# GniMp3.net
KiCad netlist of a schematic drawn in Altium Designer
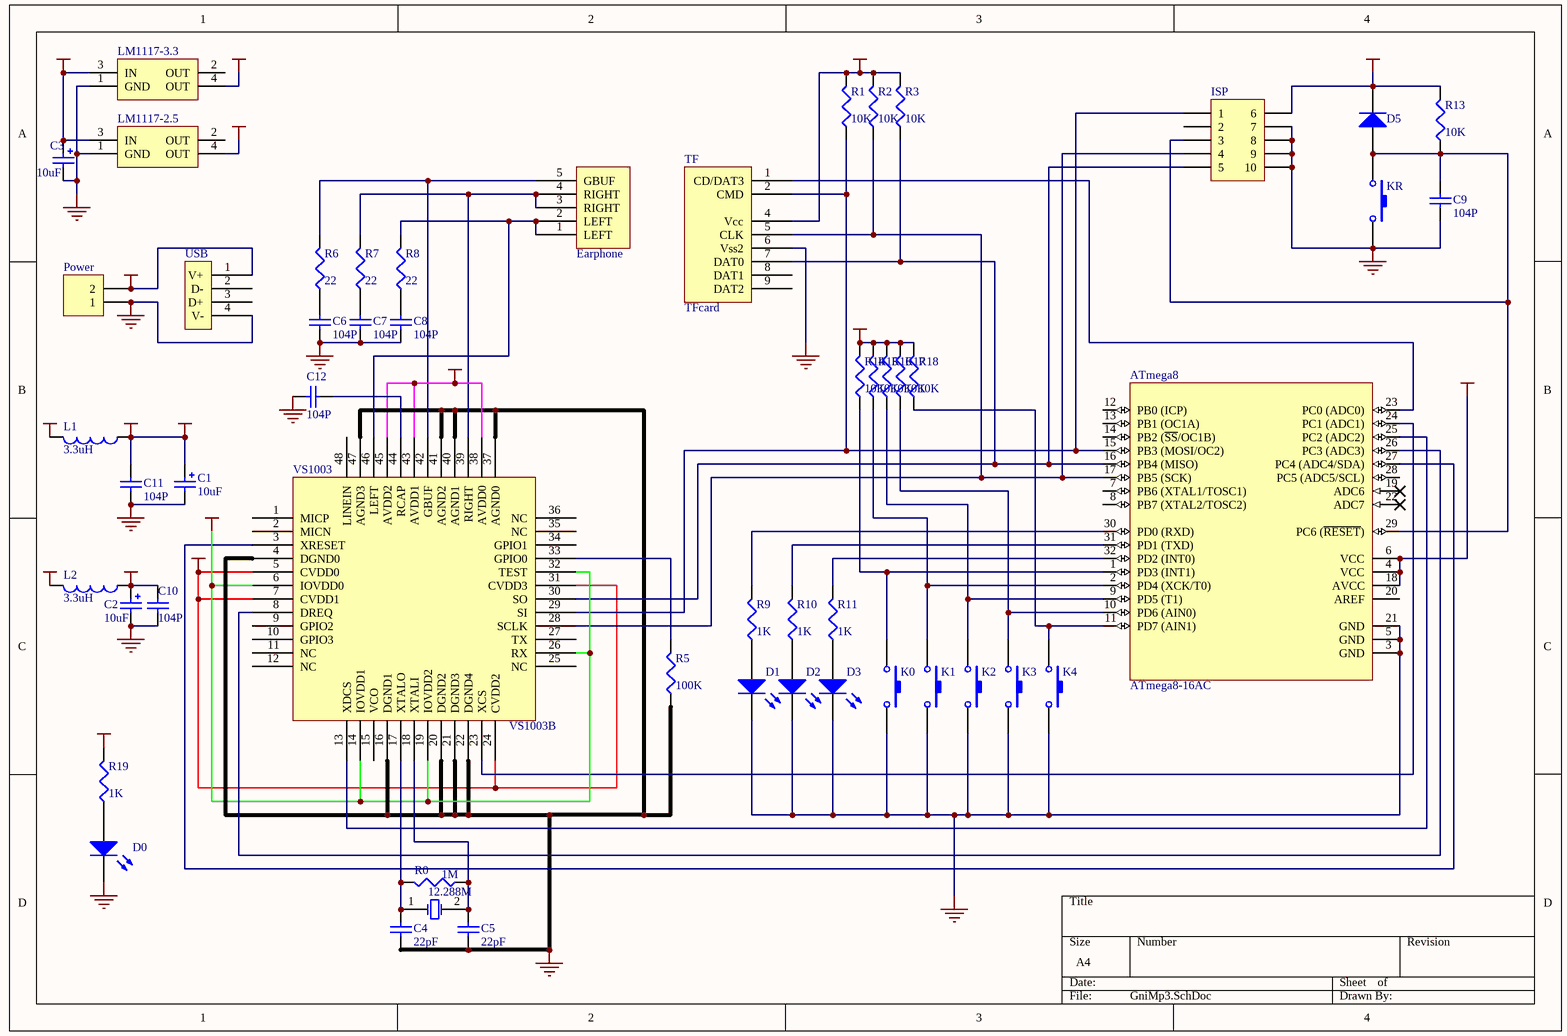
[diagram p0: GniMp3.SchDoc]

(export (version "E")
  (design (tool "Eeschema 10.0.6"))
  (components
    (comp (ref "12.288M")
      (value "XTAL")
      (footprint "RAD-0.2")
      (description "Crystal Oscillator")
      (fields (field (name "PUBLISHER") "Altium Limited"))
      (libsource (lib "Miscellaneous Devices") (part "XTAL"))
    )
    (comp (ref "ATmega8")
      (value "ATmega8-16AC")
      (footprint "32A")
      (description "8-Bit AVR Microcontroller with 8K Bytes of In-System Programmable Flash Memory")
      (fields (field (name "PUBLISHER") "Altium Limited"))
      (libsource (lib "Atmel Microcontroller 8-Bit AVR") (part "ATmega8-16AC"))
    )
    (comp (ref "C1")
      (value "10uF")
      (footprint "CC3225-1210")
      (description "Polarized Capacitor (Surface Mount)")
      (fields (field (name "Comment") "Cap Pol3") (field (name "PUBLISHER") "Altium Limited"))
      (libsource (lib "Miscellaneous Devices") (part "Cap Pol3"))
    )
    (comp (ref "C2")
      (value "10uF")
      (footprint "CR3225-1210")
      (description "Polarized Capacitor (Surface Mount)")
      (fields (field (name "Comment") "Cap Pol3") (field (name "PUBLISHER") "Altium Limited"))
      (libsource (lib "Miscellaneous Devices") (part "Cap Pol3"))
    )
    (comp (ref "C3")
      (value "10uF")
      (footprint "CR3225-1210")
      (description "Polarized Capacitor (Surface Mount)")
      (fields (field (name "Comment") "Cap Pol3") (field (name "PUBLISHER") "Altium Limited"))
      (libsource (lib "Miscellaneous Devices") (part "Cap Pol3"))
    )
    (comp (ref "C4")
      (value "22pF")
      (footprint "CR2012-0805")
      (description "Capacitor (Semiconductor SIM Model)")
      (fields (field (name "Comment") "Cap Semi") (field (name "PUBLISHER") "Altium Limited"))
      (libsource (lib "Miscellaneous Devices") (part "Cap Semi"))
    )
    (comp (ref "C5")
      (value "22pF")
      (footprint "CR2012-0805")
      (description "Capacitor (Semiconductor SIM Model)")
      (fields (field (name "Comment") "Cap Semi") (field (name "PUBLISHER") "Altium Limited"))
      (libsource (lib "Miscellaneous Devices") (part "Cap Semi"))
    )
    (comp (ref "C6")
      (value "104P")
      (footprint "CR2012-0805")
      (description "Capacitor (Semiconductor SIM Model)")
      (fields (field (name "Comment") "Cap Semi") (field (name "PUBLISHER") "Altium Limited"))
      (libsource (lib "Miscellaneous Devices") (part "Cap Semi"))
    )
    (comp (ref "C7")
      (value "104P")
      (footprint "CR2012-0805")
      (description "Capacitor (Semiconductor SIM Model)")
      (fields (field (name "Comment") "Cap Semi") (field (name "PUBLISHER") "Altium Limited"))
      (libsource (lib "Miscellaneous Devices") (part "Cap Semi"))
    )
    (comp (ref "C8")
      (value "104P")
      (footprint "CR2012-0805")
      (description "Capacitor (Semiconductor SIM Model)")
      (fields (field (name "Comment") "Cap Semi") (field (name "PUBLISHER") "Altium Limited"))
      (libsource (lib "Miscellaneous Devices") (part "Cap Semi"))
    )
    (comp (ref "C9")
      (value "104P")
      (footprint "CR2012-0805")
      (description "Capacitor (Semiconductor SIM Model)")
      (fields (field (name "Comment") "Cap Semi") (field (name "PUBLISHER") "Altium Limited"))
      (libsource (lib "Miscellaneous Devices") (part "Cap Semi"))
    )
    (comp (ref "C10")
      (value "104P")
      (footprint "CR2012-0805")
      (description "Capacitor (Semiconductor SIM Model)")
      (fields (field (name "Comment") "Cap Semi") (field (name "PUBLISHER") "Altium Limited"))
      (libsource (lib "Miscellaneous Devices") (part "Cap Semi"))
    )
    (comp (ref "C11")
      (value "104P")
      (footprint "CR2012-0805")
      (description "Capacitor (Semiconductor SIM Model)")
      (fields (field (name "Comment") "Cap Semi") (field (name "PUBLISHER") "Altium Limited"))
      (libsource (lib "Miscellaneous Devices") (part "Cap Semi"))
    )
    (comp (ref "C12")
      (value "104P")
      (footprint "CR2012-0805")
      (description "Capacitor (Semiconductor SIM Model)")
      (fields (field (name "Comment") "Cap Semi") (field (name "PUBLISHER") "Altium Limited"))
      (libsource (lib "Miscellaneous Devices") (part "Cap Semi"))
    )
    (comp (ref "D0")
      (value "LED2")
      (footprint "R2012-0805")
      (description "Typical RED, GREEN, YELLOW, AMBER GaAs LED")
      (fields (field (name "PUBLISHER") "Altium Limited"))
      (libsource (lib "Miscellaneous Devices") (part "LED2"))
    )
    (comp (ref "D1")
      (value "LED2")
      (footprint "R2012-0805")
      (description "Typical RED, GREEN, YELLOW, AMBER GaAs LED")
      (fields (field (name "PUBLISHER") "Altium Limited"))
      (libsource (lib "Miscellaneous Devices") (part "LED2"))
    )
    (comp (ref "D2")
      (value "LED2")
      (footprint "R2012-0805")
      (description "Typical RED, GREEN, YELLOW, AMBER GaAs LED")
      (fields (field (name "PUBLISHER") "Altium Limited"))
      (libsource (lib "Miscellaneous Devices") (part "LED2"))
    )
    (comp (ref "D3")
      (value "LED2")
      (footprint "R2012-0805")
      (description "Typical RED, GREEN, YELLOW, AMBER GaAs LED")
      (fields (field (name "PUBLISHER") "Altium Limited"))
      (libsource (lib "Miscellaneous Devices") (part "LED2"))
    )
    (comp (ref "D5")
      (value "Diode 1N4148")
      (footprint "DSO-F2/D6.1")
      (description "High Conductance Fast Diode")
      (fields (field (name "PUBLISHER") "Altium Limited"))
      (libsource (lib "Miscellaneous Devices") (part "Diode 1N4148"))
    )
    (comp (ref "Earphone")
      (value "Earphone")
      (footprint "Earphone")
      (libsource (lib "Earphone") (part "Earphone"))
    )
    (comp (ref "ISP")
      (value "Header 5X2A")
      (footprint "HDR2X5_CEN")
      (description "Header, 5-Pin, Dual row")
      (fields (field (name "PUBLISHER") "Altium Limited"))
      (libsource (lib "Miscellaneous Connectors") (part "Header 5X2A"))
    )
    (comp (ref "K0")
      (value "SW-PB")
      (footprint "Key")
      (description "Switch")
      (fields (field (name "PUBLISHER") "Altium Limited"))
      (libsource (lib "Miscellaneous Devices") (part "SW-PB"))
    )
    (comp (ref "K1")
      (value "SW-PB")
      (footprint "Key")
      (description "Switch")
      (fields (field (name "PUBLISHER") "Altium Limited"))
      (libsource (lib "Miscellaneous Devices") (part "SW-PB"))
    )
    (comp (ref "K2")
      (value "SW-PB")
      (footprint "Key")
      (description "Switch")
      (fields (field (name "PUBLISHER") "Altium Limited"))
      (libsource (lib "Miscellaneous Devices") (part "SW-PB"))
    )
    (comp (ref "K3")
      (value "SW-PB")
      (footprint "Key")
      (description "Switch")
      (fields (field (name "PUBLISHER") "Altium Limited"))
      (libsource (lib "Miscellaneous Devices") (part "SW-PB"))
    )
    (comp (ref "K4")
      (value "SW-PB")
      (footprint "Key")
      (description "Switch")
      (fields (field (name "PUBLISHER") "Altium Limited"))
      (libsource (lib "Miscellaneous Devices") (part "SW-PB"))
    )
    (comp (ref "KR")
      (value "SW-PB")
      (footprint "Key")
      (description "Switch")
      (fields (field (name "PUBLISHER") "Altium Limited"))
      (libsource (lib "Miscellaneous Devices") (part "SW-PB"))
    )
    (comp (ref "L1")
      (value "3.3uH")
      (footprint "R2012-0805")
      (description "Inductor")
      (fields (field (name "PUBLISHER") "Altium Limited"))
      (libsource (lib "Miscellaneous Devices") (part "Inductor"))
    )
    (comp (ref "L2")
      (value "3.3uH")
      (footprint "R2012-0805")
      (description "Inductor")
      (fields (field (name "PUBLISHER") "Altium Limited"))
      (libsource (lib "Miscellaneous Devices") (part "Inductor"))
    )
    (comp (ref "LM1117-2.5")
      (value "REG1117-5")
      (footprint "ZZ311")
      (description "800mA and 1A Low Dropout Positive Regulator 2.85V, 3.3V, 5V, and Adjustable")
      (fields (field (name "PUBLISHER") "Altium Limited"))
      (libsource (lib "BB Power Mgt Voltage Regulator") (part "REG1117-5"))
    )
    (comp (ref "LM1117-3.3")
      (value "REG1117-5")
      (footprint "ZZ311")
      (description "800mA and 1A Low Dropout Positive Regulator 2.85V, 3.3V, 5V, and Adjustable")
      (fields (field (name "PUBLISHER") "Altium Limited"))
      (libsource (lib "BB Power Mgt Voltage Regulator") (part "REG1117-5"))
    )
    (comp (ref "Power")
      (value "Header 2")
      (footprint "HDR1X2")
      (description "Header, 2-Pin")
      (fields (field (name "PUBLISHER") "Altium Limited"))
      (libsource (lib "Miscellaneous Connectors") (part "Header 2"))
    )
    (comp (ref "R0")
      (value "1M")
      (footprint "R2012-0805")
      (description "Resistor")
      (fields (field (name "Comment") "Res3") (field (name "PUBLISHER") "Altium Limited"))
      (libsource (lib "Miscellaneous Devices") (part "Res3"))
    )
    (comp (ref "R1")
      (value "10K")
      (footprint "R2012-0805")
      (description "Resistor")
      (fields (field (name "Comment") "Res3") (field (name "PUBLISHER") "Altium Limited"))
      (libsource (lib "Miscellaneous Devices") (part "Res3"))
    )
    (comp (ref "R2")
      (value "10K")
      (footprint "R2012-0805")
      (description "Resistor")
      (fields (field (name "Comment") "Res3") (field (name "PUBLISHER") "Altium Limited"))
      (libsource (lib "Miscellaneous Devices") (part "Res3"))
    )
    (comp (ref "R3")
      (value "10K")
      (footprint "R2012-0805")
      (description "Resistor")
      (fields (field (name "Comment") "Res3") (field (name "PUBLISHER") "Altium Limited"))
      (libsource (lib "Miscellaneous Devices") (part "Res3"))
    )
    (comp (ref "R5")
      (value "100K")
      (footprint "R2012-0805")
      (description "Resistor")
      (fields (field (name "Comment") "Res3") (field (name "PUBLISHER") "Altium Limited"))
      (libsource (lib "Miscellaneous Devices") (part "Res3"))
    )
    (comp (ref "R6")
      (value "22")
      (footprint "R2012-0805")
      (description "Resistor")
      (fields (field (name "Comment") "Res3") (field (name "PUBLISHER") "Altium Limited"))
      (libsource (lib "Miscellaneous Devices") (part "Res3"))
    )
    (comp (ref "R7")
      (value "22")
      (footprint "R2012-0805")
      (description "Resistor")
      (fields (field (name "Comment") "Res3") (field (name "PUBLISHER") "Altium Limited"))
      (libsource (lib "Miscellaneous Devices") (part "Res3"))
    )
    (comp (ref "R8")
      (value "22")
      (footprint "R2012-0805")
      (description "Resistor")
      (fields (field (name "Comment") "Res3") (field (name "PUBLISHER") "Altium Limited"))
      (libsource (lib "Miscellaneous Devices") (part "Res3"))
    )
    (comp (ref "R9")
      (value "1K")
      (footprint "R2012-0805")
      (description "Resistor")
      (fields (field (name "Comment") "Res3") (field (name "PUBLISHER") "Altium Limited"))
      (libsource (lib "Miscellaneous Devices") (part "Res3"))
    )
    (comp (ref "R10")
      (value "1K")
      (footprint "R2012-0805")
      (description "Resistor")
      (fields (field (name "Comment") "Res3") (field (name "PUBLISHER") "Altium Limited"))
      (libsource (lib "Miscellaneous Devices") (part "Res3"))
    )
    (comp (ref "R11")
      (value "1K")
      (footprint "R2012-0805")
      (description "Resistor")
      (fields (field (name "Comment") "Res3") (field (name "PUBLISHER") "Altium Limited"))
      (libsource (lib "Miscellaneous Devices") (part "Res3"))
    )
    (comp (ref "R13")
      (value "10K")
      (footprint "R2012-0805")
      (description "Resistor")
      (fields (field (name "Comment") "Res3") (field (name "PUBLISHER") "Altium Limited"))
      (libsource (lib "Miscellaneous Devices") (part "Res3"))
    )
    (comp (ref "R14")
      (value "10K")
      (footprint "R2012-0805")
      (description "Resistor")
      (fields (field (name "Comment") "Res3") (field (name "PUBLISHER") "Altium Limited"))
      (libsource (lib "Miscellaneous Devices") (part "Res3"))
    )
    (comp (ref "R15")
      (value "10K")
      (footprint "R2012-0805")
      (description "Resistor")
      (fields (field (name "Comment") "Res3") (field (name "PUBLISHER") "Altium Limited"))
      (libsource (lib "Miscellaneous Devices") (part "Res3"))
    )
    (comp (ref "R16")
      (value "10K")
      (footprint "R2012-0805")
      (description "Resistor")
      (fields (field (name "Comment") "Res3") (field (name "PUBLISHER") "Altium Limited"))
      (libsource (lib "Miscellaneous Devices") (part "Res3"))
    )
    (comp (ref "R17")
      (value "10K")
      (footprint "R2012-0805")
      (description "Resistor")
      (fields (field (name "Comment") "Res3") (field (name "PUBLISHER") "Altium Limited"))
      (libsource (lib "Miscellaneous Devices") (part "Res3"))
    )
    (comp (ref "R18")
      (value "10K")
      (footprint "R2012-0805")
      (description "Resistor")
      (fields (field (name "Comment") "Res3") (field (name "PUBLISHER") "Altium Limited"))
      (libsource (lib "Miscellaneous Devices") (part "Res3"))
    )
    (comp (ref "R19")
      (value "1K")
      (footprint "R2012-0805")
      (description "Resistor")
      (fields (field (name "Comment") "Res3") (field (name "PUBLISHER") "Altium Limited"))
      (libsource (lib "Miscellaneous Devices") (part "Res3"))
    )
    (comp (ref "TF") (value "TFcard") (footprint "TF Card") (libsource (lib "TFCARD") (part "TFcard")))
    (comp (ref "USB") (value "USB") (footprint "mini_USB") (libsource (lib "USB") (part "USB")))
    (comp (ref "VS1003") (value "VS1003B") (footprint "TQFP-48") (libsource (lib "VS1003") (part "VS1003B")))
  )
  (nets
    (net (code "1") (name "2.5v") (class "Default")
      (node (ref "L2") (pin "2") (pinfunction "2_2") (pintype "passive"))
      (node (ref "LM1117-2.5") (pin "4") (pinfunction "OUT_4") (pintype "power_in"))
    )
    (net (code "2") (name "3.3v") (class "Default")
      (node (ref "ATmega8") (pin "18") (pinfunction "AVCC_18") (pintype "power_in"))
      (node (ref "ATmega8") (pin "4") (pinfunction "VCC_4") (pintype "power_in"))
      (node (ref "ATmega8") (pin "6") (pinfunction "VCC_6") (pintype "power_in"))
      (node (ref "D5") (pin "2") (pinfunction "K_2") (pintype "passive"))
      (node (ref "ISP") (pin "6") (pinfunction "6_6") (pintype "passive"))
      (node (ref "L1") (pin "2") (pinfunction "2_2") (pintype "passive"))
      (node (ref "LM1117-3.3") (pin "4") (pinfunction "OUT_4") (pintype "power_in"))
      (node (ref "R1") (pin "2") (pinfunction "2_2") (pintype "passive"))
      (node (ref "R13") (pin "2") (pinfunction "2_2") (pintype "passive"))
      (node (ref "R14") (pin "2") (pinfunction "2_2") (pintype "passive"))
      (node (ref "R15") (pin "2") (pinfunction "2_2") (pintype "passive"))
      (node (ref "R16") (pin "2") (pinfunction "2_2") (pintype "passive"))
      (node (ref "R17") (pin "2") (pinfunction "2_2") (pintype "passive"))
      (node (ref "R18") (pin "2") (pinfunction "2_2") (pintype "passive"))
      (node (ref "R2") (pin "2") (pinfunction "2_2") (pintype "passive"))
      (node (ref "R3") (pin "2") (pinfunction "2_2") (pintype "passive"))
      (node (ref "TF") (pin "4") (pinfunction "Vcc_4") (pintype "passive"))
    )
    (net (code "3") (name "AVDD") (class "Default")
      (node (ref "C1") (pin "1") (pinfunction "1_1") (pintype "passive"))
      (node (ref "C11") (pin "2") (pinfunction "2_2") (pintype "passive"))
      (node (ref "L1") (pin "1") (pinfunction "1_1") (pintype "passive"))
      (node (ref "VS1003") (pin "14") (pinfunction "IOVDD1_14") (pintype "passive"))
      (node (ref "VS1003") (pin "19") (pinfunction "IOVDD2_19") (pintype "passive"))
      (node (ref "VS1003") (pin "26") (pinfunction "RX_26") (pintype "passive"))
      (node (ref "VS1003") (pin "32") (pinfunction "TEST_32") (pintype "passive"))
      (node (ref "VS1003") (pin "38") (pinfunction "AVDD0_38") (pintype "passive"))
      (node (ref "VS1003") (pin "43") (pinfunction "AVDD1_43") (pintype "passive"))
      (node (ref "VS1003") (pin "45") (pinfunction "AVDD2_45") (pintype "passive"))
      (node (ref "VS1003") (pin "6") (pinfunction "IOVDD0_6") (pintype "passive"))
    )
    (net (code "4") (name "CVDD") (class "Default")
      (node (ref "C10") (pin "2") (pinfunction "2_2") (pintype "passive"))
      (node (ref "C2") (pin "1") (pinfunction "1_1") (pintype "passive"))
      (node (ref "L2") (pin "1") (pinfunction "1_1") (pintype "passive"))
      (node (ref "VS1003") (pin "24") (pinfunction "CVDD2_24") (pintype "passive"))
      (node (ref "VS1003") (pin "31") (pinfunction "CVDD3_31") (pintype "passive"))
      (node (ref "VS1003") (pin "5") (pinfunction "CVDD0_5") (pintype "passive"))
      (node (ref "VS1003") (pin "7") (pinfunction "CVDD1_7") (pintype "passive"))
    )
    (net (code "5") (name "GND") (class "Default")
      (node (ref "ATmega8") (pin "21") (pinfunction "GND_21") (pintype "power_in"))
      (node (ref "ATmega8") (pin "3") (pinfunction "GND_3") (pintype "power_in"))
      (node (ref "ATmega8") (pin "5") (pinfunction "GND_5") (pintype "power_in"))
      (node (ref "C1") (pin "2") (pinfunction "2_2") (pintype "passive"))
      (node (ref "C10") (pin "1") (pinfunction "1_1") (pintype "passive"))
      (node (ref "C11") (pin "1") (pinfunction "1_1") (pintype "passive"))
      (node (ref "C12") (pin "2") (pinfunction "2_2") (pintype "passive"))
      (node (ref "C2") (pin "2") (pinfunction "2_2") (pintype "passive"))
      (node (ref "C3") (pin "2") (pinfunction "2_2") (pintype "passive"))
      (node (ref "C4") (pin "1") (pinfunction "1_1") (pintype "passive"))
      (node (ref "C5") (pin "2") (pinfunction "2_2") (pintype "passive"))
      (node (ref "C6") (pin "1") (pinfunction "1_1") (pintype "passive"))
      (node (ref "C7") (pin "1") (pinfunction "1_1") (pintype "passive"))
      (node (ref "C8") (pin "1") (pinfunction "1_1") (pintype "passive"))
      (node (ref "C9") (pin "1") (pinfunction "1_1") (pintype "passive"))
      (node (ref "D0") (pin "2") (pinfunction "K_2") (pintype "passive"))
      (node (ref "D1") (pin "2") (pinfunction "K_2") (pintype "passive"))
      (node (ref "D2") (pin "2") (pinfunction "K_2") (pintype "passive"))
      (node (ref "D3") (pin "2") (pinfunction "K_2") (pintype "passive"))
      (node (ref "ISP") (pin "10") (pinfunction "10_10") (pintype "passive"))
      (node (ref "ISP") (pin "7") (pinfunction "7_7") (pintype "passive"))
      (node (ref "ISP") (pin "8") (pinfunction "8_8") (pintype "passive"))
      (node (ref "ISP") (pin "9") (pinfunction "9_9") (pintype "passive"))
      (node (ref "K0") (pin "2") (pinfunction "2_2") (pintype "passive"))
      (node (ref "K1") (pin "2") (pinfunction "2_2") (pintype "passive"))
      (node (ref "K2") (pin "2") (pinfunction "2_2") (pintype "passive"))
      (node (ref "K3") (pin "2") (pinfunction "2_2") (pintype "passive"))
      (node (ref "K4") (pin "2") (pinfunction "2_2") (pintype "passive"))
      (node (ref "KR") (pin "2") (pinfunction "2_2") (pintype "passive"))
      (node (ref "LM1117-2.5") (pin "1") (pinfunction "GND_1") (pintype "power_in"))
      (node (ref "LM1117-3.3") (pin "1") (pinfunction "GND_1") (pintype "power_in"))
      (node (ref "Power") (pin "1") (pinfunction "1_1") (pintype "passive"))
      (node (ref "R5") (pin "1") (pinfunction "1_1") (pintype "passive"))
      (node (ref "TF") (pin "6") (pinfunction "Vss2_6") (pintype "passive"))
      (node (ref "USB") (pin "4") (pinfunction "V-_4") (pintype "passive"))
      (node (ref "VS1003") (pin "16") (pinfunction "DGND1_16") (pintype "passive"))
      (node (ref "VS1003") (pin "20") (pinfunction "DGND2_20") (pintype "passive"))
      (node (ref "VS1003") (pin "21") (pinfunction "DGND3_21") (pintype "passive"))
      (node (ref "VS1003") (pin "22") (pinfunction "DGND4_22") (pintype "passive"))
      (node (ref "VS1003") (pin "37") (pinfunction "AGND0_37") (pintype "passive"))
      (node (ref "VS1003") (pin "4") (pinfunction "DGND0_4") (pintype "passive"))
      (node (ref "VS1003") (pin "40") (pinfunction "AGND1_40") (pintype "passive"))
      (node (ref "VS1003") (pin "41") (pinfunction "AGND2_41") (pintype "passive"))
      (node (ref "VS1003") (pin "47") (pinfunction "AGND3_47") (pintype "passive"))
    )
    (net (code "6") (name "Net-(12.288M-OSC1)") (class "Default")
      (node (ref "12.288M") (pin "1") (pinfunction "OSC1_1") (pintype "passive"))
      (node (ref "C4") (pin "2") (pinfunction "2_2") (pintype "passive"))
      (node (ref "R0") (pin "2") (pinfunction "2_2") (pintype "passive"))
      (node (ref "VS1003") (pin "17") (pinfunction "XTALO_17") (pintype "passive"))
    )
    (net (code "7") (name "Net-(12.288M-OSC2)") (class "Default")
      (node (ref "12.288M") (pin "2") (pinfunction "OSC2_2") (pintype "passive"))
      (node (ref "C5") (pin "1") (pinfunction "1_1") (pintype "passive"))
      (node (ref "R0") (pin "1") (pinfunction "1_1") (pintype "passive"))
      (node (ref "VS1003") (pin "18") (pinfunction "XTALI_18") (pintype "passive"))
    )
    (net (code "8") (name "Net-(ATmega8-PB3_(MOSI{slash}OC2))") (class "Default")
      (node (ref "ATmega8") (pin "15") (pinfunction "PB3_(MOSI/OC2)_15") (pintype "bidirectional"))
      (node (ref "ISP") (pin "1") (pinfunction "1_1") (pintype "passive"))
      (node (ref "R1") (pin "1") (pinfunction "1_1") (pintype "passive"))
      (node (ref "TF") (pin "2") (pinfunction "CMD_2") (pintype "passive"))
      (node (ref "VS1003") (pin "29") (pinfunction "SI_29") (pintype "passive"))
    )
    (net (code "9") (name "Net-(ATmega8-PB4_(MISO))") (class "Default")
      (node (ref "ATmega8") (pin "16") (pinfunction "PB4_(MISO)_16") (pintype "bidirectional"))
      (node (ref "ISP") (pin "5") (pinfunction "5_5") (pintype "passive"))
      (node (ref "R3") (pin "1") (pinfunction "1_1") (pintype "passive"))
      (node (ref "TF") (pin "7") (pinfunction "DAT0_7") (pintype "passive"))
      (node (ref "VS1003") (pin "30") (pinfunction "SO_30") (pintype "passive"))
    )
    (net (code "10") (name "Net-(ATmega8-PB5_(SCK))") (class "Default")
      (node (ref "ATmega8") (pin "17") (pinfunction "PB5_(SCK)_17") (pintype "bidirectional"))
      (node (ref "ISP") (pin "4") (pinfunction "4_4") (pintype "passive"))
      (node (ref "R2") (pin "1") (pinfunction "1_1") (pintype "passive"))
      (node (ref "TF") (pin "5") (pinfunction "CLK_5") (pintype "passive"))
      (node (ref "VS1003") (pin "28") (pinfunction "SCLK_28") (pintype "passive"))
    )
    (net (code "11") (name "Net-(ATmega8-PC0_(ADC0))") (class "Default")
      (node (ref "ATmega8") (pin "23") (pinfunction "PC0_(ADC0)_23") (pintype "bidirectional"))
      (node (ref "TF") (pin "1") (pinfunction "CD/DAT3_1") (pintype "passive"))
    )
    (net (code "12") (name "Net-(ATmega8-PC1_(ADC1))") (class "Default")
      (node (ref "ATmega8") (pin "24") (pinfunction "PC1_(ADC1)_24") (pintype "bidirectional"))
      (node (ref "VS1003") (pin "23") (pinfunction "XCS_23") (pintype "passive"))
    )
    (net (code "13") (name "Net-(ATmega8-PC2_(ADC2))") (class "Default")
      (node (ref "ATmega8") (pin "25") (pinfunction "PC2_(ADC2)_25") (pintype "bidirectional"))
      (node (ref "VS1003") (pin "13") (pinfunction "XDCS_13") (pintype "passive"))
    )
    (net (code "14") (name "Net-(ATmega8-PC3_(ADC3))") (class "Default")
      (node (ref "ATmega8") (pin "26") (pinfunction "PC3_(ADC3)_26") (pintype "bidirectional"))
      (node (ref "VS1003") (pin "8") (pinfunction "DREQ_8") (pintype "passive"))
    )
    (net (code "15") (name "Net-(ATmega8-PC4_(ADC4{slash}SDA))") (class "Default")
      (node (ref "ATmega8") (pin "27") (pinfunction "PC4_(ADC4/SDA)_27") (pintype "bidirectional"))
      (node (ref "VS1003") (pin "3") (pinfunction "XRESET_3") (pintype "passive"))
    )
    (net (code "16") (name "Net-(ATmega8-PC6_(~{RESET}))") (class "Default")
      (node (ref "ATmega8") (pin "29") (pinfunction "PC6_(~{RESET})_29") (pintype "bidirectional"))
      (node (ref "C9") (pin "2") (pinfunction "2_2") (pintype "passive"))
      (node (ref "D5") (pin "1") (pinfunction "A_1") (pintype "passive"))
      (node (ref "ISP") (pin "3") (pinfunction "3_3") (pintype "passive"))
      (node (ref "KR") (pin "1") (pinfunction "1_1") (pintype "passive"))
      (node (ref "R13") (pin "1") (pinfunction "1_1") (pintype "passive"))
    )
    (net (code "17") (name "Net-(ATmega8-PD0_(RXD))") (class "Default")
      (node (ref "ATmega8") (pin "30") (pinfunction "PD0_(RXD)_30") (pintype "bidirectional"))
      (node (ref "R9") (pin "2") (pinfunction "2_2") (pintype "passive"))
    )
    (net (code "18") (name "Net-(ATmega8-PD1_(TXD))") (class "Default")
      (node (ref "ATmega8") (pin "31") (pinfunction "PD1_(TXD)_31") (pintype "bidirectional"))
      (node (ref "R10") (pin "2") (pinfunction "2_2") (pintype "passive"))
    )
    (net (code "19") (name "Net-(ATmega8-PD2_(INT0))") (class "Default")
      (node (ref "ATmega8") (pin "32") (pinfunction "PD2_(INT0)_32") (pintype "bidirectional"))
      (node (ref "R11") (pin "2") (pinfunction "2_2") (pintype "passive"))
    )
    (net (code "20") (name "Net-(ATmega8-PD3_(INT1))") (class "Default")
      (node (ref "ATmega8") (pin "1") (pinfunction "PD3_(INT1)_1") (pintype "bidirectional"))
      (node (ref "K0") (pin "1") (pinfunction "1_1") (pintype "passive"))
      (node (ref "R14") (pin "1") (pinfunction "1_1") (pintype "passive"))
    )
    (net (code "21") (name "Net-(ATmega8-PD4_(XCK{slash}T0))") (class "Default")
      (node (ref "ATmega8") (pin "2") (pinfunction "PD4_(XCK/T0)_2") (pintype "bidirectional"))
      (node (ref "K1") (pin "1") (pinfunction "1_1") (pintype "passive"))
      (node (ref "R15") (pin "1") (pinfunction "1_1") (pintype "passive"))
    )
    (net (code "22") (name "Net-(ATmega8-PD5_(T1))") (class "Default")
      (node (ref "ATmega8") (pin "9") (pinfunction "PD5_(T1)_9") (pintype "bidirectional"))
      (node (ref "K2") (pin "1") (pinfunction "1_1") (pintype "passive"))
      (node (ref "R16") (pin "1") (pinfunction "1_1") (pintype "passive"))
    )
    (net (code "23") (name "Net-(ATmega8-PD6_(AIN0))") (class "Default")
      (node (ref "ATmega8") (pin "10") (pinfunction "PD6_(AIN0)_10") (pintype "bidirectional"))
      (node (ref "K3") (pin "1") (pinfunction "1_1") (pintype "passive"))
      (node (ref "R17") (pin "1") (pinfunction "1_1") (pintype "passive"))
    )
    (net (code "24") (name "Net-(ATmega8-PD7_(AIN1))") (class "Default")
      (node (ref "ATmega8") (pin "11") (pinfunction "PD7_(AIN1)_11") (pintype "bidirectional"))
      (node (ref "K4") (pin "1") (pinfunction "1_1") (pintype "passive"))
      (node (ref "R18") (pin "1") (pinfunction "1_1") (pintype "passive"))
    )
    (net (code "25") (name "Net-(C6-Pad2)") (class "Default")
      (node (ref "C6") (pin "2") (pinfunction "2_2") (pintype "passive"))
      (node (ref "R6") (pin "1") (pinfunction "1_1") (pintype "passive"))
    )
    (net (code "26") (name "Net-(C7-Pad2)") (class "Default")
      (node (ref "C7") (pin "2") (pinfunction "2_2") (pintype "passive"))
      (node (ref "R7") (pin "1") (pinfunction "1_1") (pintype "passive"))
    )
    (net (code "27") (name "Net-(C8-Pad2)") (class "Default")
      (node (ref "C8") (pin "2") (pinfunction "2_2") (pintype "passive"))
      (node (ref "R8") (pin "1") (pinfunction "1_1") (pintype "passive"))
    )
    (net (code "28") (name "Net-(D0-A)") (class "Default")
      (node (ref "D0") (pin "1") (pinfunction "A_1") (pintype "passive"))
      (node (ref "R19") (pin "1") (pinfunction "1_1") (pintype "passive"))
    )
    (net (code "29") (name "Net-(D1-A)") (class "Default")
      (node (ref "D1") (pin "1") (pinfunction "A_1") (pintype "passive"))
      (node (ref "R9") (pin "1") (pinfunction "1_1") (pintype "passive"))
    )
    (net (code "30") (name "Net-(D2-A)") (class "Default")
      (node (ref "D2") (pin "1") (pinfunction "A_1") (pintype "passive"))
      (node (ref "R10") (pin "1") (pinfunction "1_1") (pintype "passive"))
    )
    (net (code "31") (name "Net-(D3-A)") (class "Default")
      (node (ref "D3") (pin "1") (pinfunction "A_1") (pintype "passive"))
      (node (ref "R11") (pin "1") (pinfunction "1_1") (pintype "passive"))
    )
    (net (code "32") (name "Net-(Earphone-GBUF)") (class "Default")
      (node (ref "Earphone") (pin "5") (pinfunction "GBUF_5") (pintype "passive"))
      (node (ref "R6") (pin "2") (pinfunction "2_2") (pintype "passive"))
      (node (ref "VS1003") (pin "42") (pinfunction "GBUF_42") (pintype "passive"))
    )
    (net (code "33") (name "Net-(VS1003-GPIO0)") (class "Default")
      (node (ref "R5") (pin "2") (pinfunction "2_2") (pintype "passive"))
      (node (ref "VS1003") (pin "33") (pinfunction "GPIO0_33") (pintype "passive"))
    )
    (net (code "34") (name "Net-(VS1003-LEFT)") (class "Default")
      (node (ref "Earphone") (pin "1") (pinfunction "LEFT_1") (pintype "passive"))
      (node (ref "Earphone") (pin "2") (pinfunction "LEFT_2") (pintype "passive"))
      (node (ref "R8") (pin "2") (pinfunction "2_2") (pintype "passive"))
      (node (ref "VS1003") (pin "46") (pinfunction "LEFT_46") (pintype "passive"))
    )
    (net (code "35") (name "Net-(VS1003-RCAP)") (class "Default")
      (node (ref "C12") (pin "1") (pinfunction "1_1") (pintype "passive"))
      (node (ref "VS1003") (pin "44") (pinfunction "RCAP_44") (pintype "passive"))
    )
    (net (code "36") (name "Net-(VS1003-RIGHT)") (class "Default")
      (node (ref "Earphone") (pin "3") (pinfunction "RIGHT_3") (pintype "passive"))
      (node (ref "Earphone") (pin "4") (pinfunction "RIGHT_4") (pintype "passive"))
      (node (ref "R7") (pin "2") (pinfunction "2_2") (pintype "passive"))
      (node (ref "VS1003") (pin "39") (pinfunction "RIGHT_39") (pintype "passive"))
    )
    (net (code "37") (name "VCC") (class "Default")
      (node (ref "C3") (pin "1") (pinfunction "1_1") (pintype "passive"))
      (node (ref "LM1117-2.5") (pin "3") (pinfunction "IN_3") (pintype "power_in"))
      (node (ref "LM1117-3.3") (pin "3") (pinfunction "IN_3") (pintype "power_in"))
      (node (ref "Power") (pin "2") (pinfunction "2_2") (pintype "passive"))
      (node (ref "R19") (pin "2") (pinfunction "2_2") (pintype "passive"))
      (node (ref "USB") (pin "1") (pinfunction "V+_1") (pintype "passive"))
    )
    (net (code "38") (name "unconnected-(ATmega8-ADC6-Pad19)") (class "Default")
      (node (ref "ATmega8") (pin "19") (pinfunction "ADC6_19") (pintype "input+no_connect"))
    )
    (net (code "39") (name "unconnected-(ATmega8-ADC7-Pad22)") (class "Default")
      (node (ref "ATmega8") (pin "22") (pinfunction "ADC7_22") (pintype "input+no_connect"))
    )
    (net (code "40") (name "unconnected-(ATmega8-AREF-Pad20)") (class "Default")
      (node (ref "ATmega8") (pin "20") (pinfunction "AREF_20") (pintype "passive"))
    )
    (net (code "41") (name "unconnected-(ATmega8-PB0_(ICP)-Pad12)") (class "Default")
      (node (ref "ATmega8") (pin "12") (pinfunction "PB0_(ICP)_12") (pintype "bidirectional"))
    )
    (net (code "42") (name "unconnected-(ATmega8-PB1_(OC1A)-Pad13)") (class "Default")
      (node (ref "ATmega8") (pin "13") (pinfunction "PB1_(OC1A)_13") (pintype "bidirectional"))
    )
    (net (code "43") (name "unconnected-(ATmega8-PB2_(~{SS}{slash}OC1B)-Pad14)") (class "Default")
      (node (ref "ATmega8") (pin "14") (pinfunction "PB2_(~{SS}/OC1B)_14") (pintype "bidirectional"))
    )
    (net (code "44") (name "unconnected-(ATmega8-PB6_(XTAL1{slash}TOSC1)-Pad7)") (class "Default")
      (node (ref "ATmega8") (pin "7") (pinfunction "PB6_(XTAL1/TOSC1)_7") (pintype "bidirectional"))
    )
    (net (code "45") (name "unconnected-(ATmega8-PB7_(XTAL2{slash}TOSC2)-Pad8)") (class "Default")
      (node (ref "ATmega8") (pin "8") (pinfunction "PB7_(XTAL2/TOSC2)_8") (pintype "bidirectional"))
    )
    (net (code "46") (name "unconnected-(ATmega8-PC5_(ADC5{slash}SCL)-Pad28)") (class "Default")
      (node (ref "ATmega8") (pin "28") (pinfunction "PC5_(ADC5/SCL)_28") (pintype "bidirectional"))
    )
    (net (code "47") (name "unconnected-(ISP-Pad2)") (class "Default")
      (node (ref "ISP") (pin "2") (pinfunction "2_2") (pintype "passive"))
    )
    (net (code "48") (name "unconnected-(LM1117-2.5-OUT-Pad2)") (class "Default")
      (node (ref "LM1117-2.5") (pin "2") (pinfunction "OUT_2") (pintype "power_in"))
    )
    (net (code "49") (name "unconnected-(LM1117-3.3-OUT-Pad2)") (class "Default")
      (node (ref "LM1117-3.3") (pin "2") (pinfunction "OUT_2") (pintype "power_in"))
    )
    (net (code "50") (name "unconnected-(TF-DAT1-Pad8)") (class "Default")
      (node (ref "TF") (pin "8") (pinfunction "DAT1_8") (pintype "passive"))
    )
    (net (code "51") (name "unconnected-(TF-DAT2-Pad9)") (class "Default")
      (node (ref "TF") (pin "9") (pinfunction "DAT2_9") (pintype "passive"))
    )
    (net (code "52") (name "unconnected-(USB-D+-Pad3)") (class "Default")
      (node (ref "USB") (pin "3") (pinfunction "D+_3") (pintype "passive"))
    )
    (net (code "53") (name "unconnected-(USB-D--Pad2)") (class "Default")
      (node (ref "USB") (pin "2") (pinfunction "D-_2") (pintype "passive"))
    )
    (net (code "54") (name "unconnected-(VS1003-GPIO1-Pad34)") (class "Default")
      (node (ref "VS1003") (pin "34") (pinfunction "GPIO1_34") (pintype "passive"))
    )
    (net (code "55") (name "unconnected-(VS1003-GPIO2-Pad9)") (class "Default")
      (node (ref "VS1003") (pin "9") (pinfunction "GPIO2_9") (pintype "passive"))
    )
    (net (code "56") (name "unconnected-(VS1003-GPIO3-Pad10)") (class "Default")
      (node (ref "VS1003") (pin "10") (pinfunction "GPIO3_10") (pintype "passive"))
    )
    (net (code "57") (name "unconnected-(VS1003-LINEIN-Pad48)") (class "Default")
      (node (ref "VS1003") (pin "48") (pinfunction "LINEIN_48") (pintype "passive"))
    )
    (net (code "58") (name "unconnected-(VS1003-MICN-Pad2)") (class "Default")
      (node (ref "VS1003") (pin "2") (pinfunction "MICN_2") (pintype "passive"))
    )
    (net (code "59") (name "unconnected-(VS1003-MICP-Pad1)") (class "Default")
      (node (ref "VS1003") (pin "1") (pinfunction "MICP_1") (pintype "passive"))
    )
    (net (code "60") (name "unconnected-(VS1003-NC-Pad11)") (class "Default")
      (node (ref "VS1003") (pin "11") (pinfunction "NC_11") (pintype "passive"))
    )
    (net (code "61") (name "unconnected-(VS1003-NC-Pad12)") (class "Default")
      (node (ref "VS1003") (pin "12") (pinfunction "NC_12") (pintype "passive"))
    )
    (net (code "62") (name "unconnected-(VS1003-NC-Pad25)") (class "Default")
      (node (ref "VS1003") (pin "25") (pinfunction "NC_25") (pintype "passive"))
    )
    (net (code "63") (name "unconnected-(VS1003-NC-Pad35)") (class "Default")
      (node (ref "VS1003") (pin "35") (pinfunction "NC_35") (pintype "passive"))
    )
    (net (code "64") (name "unconnected-(VS1003-NC-Pad36)") (class "Default")
      (node (ref "VS1003") (pin "36") (pinfunction "NC_36") (pintype "passive"))
    )
    (net (code "65") (name "unconnected-(VS1003-TX-Pad27)") (class "Default")
      (node (ref "VS1003") (pin "27") (pinfunction "TX_27") (pintype "passive"))
    )
    (net (code "66") (name "unconnected-(VS1003-VCO-Pad15)") (class "Default")
      (node (ref "VS1003") (pin "15") (pinfunction "VCO_15") (pintype "passive"))
    )
  )
)
